# Communication.net
KiCad netlist of a schematic drawn in Altium Designer
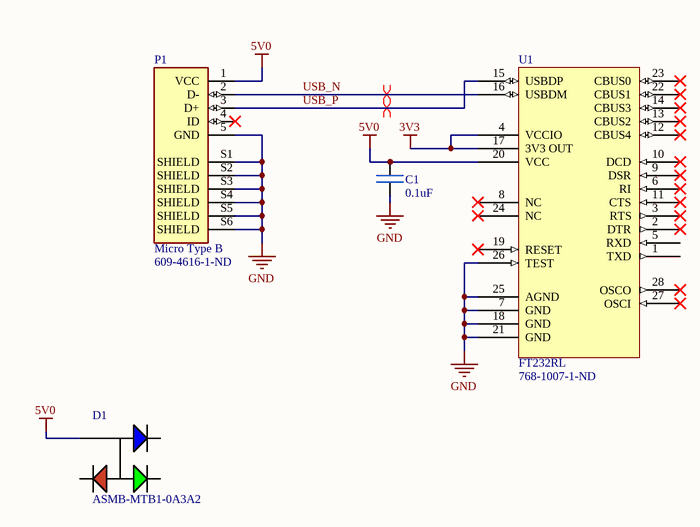
[diagram p0: Communication.SchDoc]

(export (version "E")
  (design (tool "Eeschema 10.0.6"))
  (components
    (comp (ref "C1")
      (value "0.1uF")
      (footprint "CAP0.1uF")
      (fields
        (field (name "MANUFACTURER") "Murata")
        (field (name "MANUFACTURER PART NUMBER") "GRM155R71C104KA88D")
      )
      (libsource (lib "AVRTank") (part "CAP 0.1uF"))
    )
    (comp (ref "D1")
      (value "LED_RGB_Neopixel")
      (footprint "LED_RGB")
      (description "LED RGB DIFFUSED 4PLCC SMD")
      (fields (field (name "MANUFACTURER PART NUMBER 1") "ASMB-MTB1-0A3A2"))
      (libsource (lib "SKALE_LIB") (part "LED_RGB_Neopixel"))
    )
    (comp (ref "P1")
      (value "Micro Type B")
      (footprint "FCI_10118193-0001LF")
      (description "USB Connector, 5 Contact(s), Female, Right Angle, Solder Terminal, Locking, Receptacle")
      (fields
        (field (name "MANUFACTURER") "Amphenol FCI")
        (field (name "MANUFACTURER PART NUMBER") "10118193-0001LF")
        (field (name "SUPPLIER PART NUMBER 1") "609-4616-1-ND")
      )
      (libsource (lib "HORNET_MOTOR_CONTROLLER") (part "USB Connector"))
    )
    (comp (ref "U1")
      (value "FT232RL")
      (footprint "FT232RL")
      (description "USB Bus Controller, CMOS, PDSO28")
      (fields
        (field (name "MANUFACTURER") "FTDI")
        (field (name "MANUFACTURER PART NUMBER") "FT232RL-REEL")
        (field (name "SUPPLIER PART NUMBER 1") "768-1007-1-ND")
      )
      (libsource (lib "HORNET_MOTOR_CONTROLLER") (part "FT232RL"))
    )
  )
  (nets
    (net (code "1") (name "/USB_N") (class "Default")
      (node (ref "P1") (pin "2") (pinfunction "D-_2") (pintype "bidirectional"))
      (node (ref "U1") (pin "16") (pinfunction "USBDM_16") (pintype "bidirectional"))
    )
    (net (code "2") (name "/USB_P") (class "Default")
      (node (ref "P1") (pin "3") (pinfunction "D+_3") (pintype "bidirectional"))
      (node (ref "U1") (pin "15") (pinfunction "USBDP_15") (pintype "bidirectional"))
    )
    (net (code "3") (name "3V3") (class "Default")
      (node (ref "U1") (pin "17") (pinfunction "3V3_OUT_17") (pintype "power_in"))
      (node (ref "U1") (pin "4") (pinfunction "VCCIO_4") (pintype "power_in"))
    )
    (net (code "4") (name "5V0") (class "Default")
      (node (ref "C1") (pin "1") (pintype "passive"))
      (node (ref "D1") (pin "4") (pinfunction "COMMON_ANODE_4") (pintype "passive"))
      (node (ref "P1") (pin "1") (pinfunction "VCC_1") (pintype "power_in"))
      (node (ref "U1") (pin "20") (pinfunction "VCC_20") (pintype "power_in"))
    )
    (net (code "5") (name "GND") (class "Default")
      (node (ref "C1") (pin "2") (pinfunction "08_2") (pintype "passive"))
      (node (ref "P1") (pin "5") (pinfunction "GND_5") (pintype "power_in"))
      (node (ref "P1") (pin "S1") (pinfunction "SHIELD_S1") (pintype "passive"))
      (node (ref "P1") (pin "S2") (pinfunction "SHIELD_S2") (pintype "passive"))
      (node (ref "P1") (pin "S3") (pinfunction "SHIELD_S3") (pintype "passive"))
      (node (ref "P1") (pin "S4") (pinfunction "SHIELD_S4") (pintype "passive"))
      (node (ref "P1") (pin "S5") (pinfunction "SHIELD_S5") (pintype "passive"))
      (node (ref "P1") (pin "S6") (pinfunction "SHIELD_S6") (pintype "passive"))
      (node (ref "U1") (pin "18") (pinfunction "GND_18") (pintype "power_in"))
      (node (ref "U1") (pin "21") (pinfunction "GND_21") (pintype "power_in"))
      (node (ref "U1") (pin "25") (pinfunction "AGND_25") (pintype "power_in"))
      (node (ref "U1") (pin "26") (pinfunction "TEST_26") (pintype "input"))
      (node (ref "U1") (pin "7") (pinfunction "GND_7") (pintype "power_in"))
    )
    (net (code "6") (name "unconnected-(D1-CATHODE_(BLUE)-Pad3)") (class "Default")
      (node (ref "D1") (pin "3") (pinfunction "CATHODE_(BLUE)_3") (pintype "passive"))
    )
    (net (code "7") (name "unconnected-(D1-CATHODE_(GREEN)-Pad2)") (class "Default")
      (node (ref "D1") (pin "2") (pinfunction "CATHODE_(GREEN)_2") (pintype "passive"))
    )
    (net (code "8") (name "unconnected-(D1-CATHODE_(RED)-Pad1)") (class "Default")
      (node (ref "D1") (pin "1") (pinfunction "CATHODE_(RED)_1") (pintype "passive"))
    )
    (net (code "9") (name "unconnected-(P1-ID-Pad4)") (class "Default")
      (node (ref "P1") (pin "4") (pinfunction "ID_4") (pintype "bidirectional+no_connect"))
    )
    (net (code "10") (name "unconnected-(U1-CBUS0-Pad23)") (class "Default")
      (node (ref "U1") (pin "23") (pinfunction "CBUS0_23") (pintype "bidirectional+no_connect"))
    )
    (net (code "11") (name "unconnected-(U1-CBUS1-Pad22)") (class "Default")
      (node (ref "U1") (pin "22") (pinfunction "CBUS1_22") (pintype "bidirectional+no_connect"))
    )
    (net (code "12") (name "unconnected-(U1-CBUS2-Pad13)") (class "Default")
      (node (ref "U1") (pin "13") (pinfunction "CBUS2_13") (pintype "bidirectional+no_connect"))
    )
    (net (code "13") (name "unconnected-(U1-CBUS3-Pad14)") (class "Default")
      (node (ref "U1") (pin "14") (pinfunction "CBUS3_14") (pintype "bidirectional+no_connect"))
    )
    (net (code "14") (name "unconnected-(U1-CBUS4-Pad12)") (class "Default")
      (node (ref "U1") (pin "12") (pinfunction "CBUS4_12") (pintype "bidirectional+no_connect"))
    )
    (net (code "15") (name "unconnected-(U1-CTS-Pad11)") (class "Default")
      (node (ref "U1") (pin "11") (pinfunction "CTS_11") (pintype "input+no_connect"))
    )
    (net (code "16") (name "unconnected-(U1-DCD-Pad10)") (class "Default")
      (node (ref "U1") (pin "10") (pinfunction "DCD_10") (pintype "input+no_connect"))
    )
    (net (code "17") (name "unconnected-(U1-DSR-Pad9)") (class "Default")
      (node (ref "U1") (pin "9") (pinfunction "DSR_9") (pintype "input+no_connect"))
    )
    (net (code "18") (name "unconnected-(U1-DTR-Pad2)") (class "Default")
      (node (ref "U1") (pin "2") (pinfunction "DTR_2") (pintype "output+no_connect"))
    )
    (net (code "19") (name "unconnected-(U1-NC-Pad8)") (class "Default")
      (node (ref "U1") (pin "8") (pinfunction "NC_8") (pintype "passive+no_connect"))
    )
    (net (code "20") (name "unconnected-(U1-NC-Pad24)") (class "Default")
      (node (ref "U1") (pin "24") (pinfunction "NC_24") (pintype "passive+no_connect"))
    )
    (net (code "21") (name "unconnected-(U1-OSCI-Pad27)") (class "Default")
      (node (ref "U1") (pin "27") (pinfunction "OSCI_27") (pintype "input+no_connect"))
    )
    (net (code "22") (name "unconnected-(U1-OSCO-Pad28)") (class "Default")
      (node (ref "U1") (pin "28") (pinfunction "OSCO_28") (pintype "output+no_connect"))
    )
    (net (code "23") (name "unconnected-(U1-RESET-Pad19)") (class "Default")
      (node (ref "U1") (pin "19") (pinfunction "RESET_19") (pintype "input+no_connect"))
    )
    (net (code "24") (name "unconnected-(U1-RI-Pad6)") (class "Default")
      (node (ref "U1") (pin "6") (pinfunction "RI_6") (pintype "input+no_connect"))
    )
    (net (code "25") (name "unconnected-(U1-RTS-Pad3)") (class "Default")
      (node (ref "U1") (pin "3") (pinfunction "RTS_3") (pintype "output+no_connect"))
    )
    (net (code "26") (name "unconnected-(U1-RXD-Pad5)") (class "Default")
      (node (ref "U1") (pin "5") (pinfunction "RXD_5") (pintype "input"))
    )
    (net (code "27") (name "unconnected-(U1-TXD-Pad1)") (class "Default")
      (node (ref "U1") (pin "1") (pinfunction "TXD_1") (pintype "output"))
    )
  )
)
